# double-glide.net
KiCad netlist of a schematic drawn in EAGLE
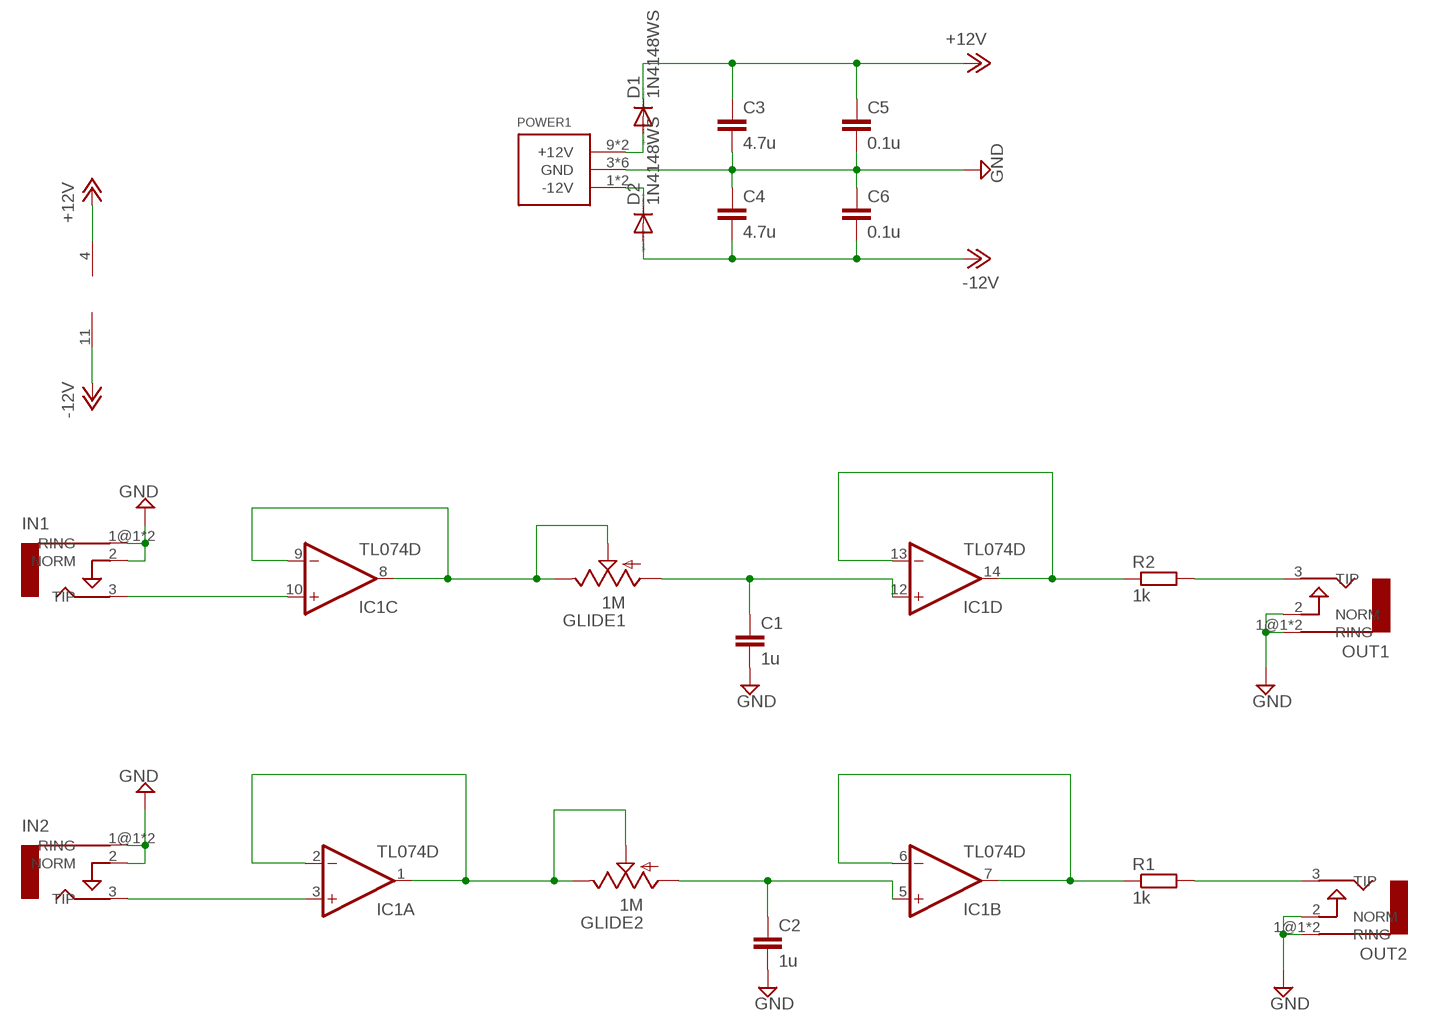
[diagram p0: schematic, sheet 1]

(export (version "E")
  (design (tool "Eeschema 10.0.6"))
  (components
    (comp (ref "C1")
      (value "1u")
      (footprint "eagle-import:C0805")
      (libsource (lib "eagle-import") (part "C-EUC0805"))
    )
    (comp (ref "C2")
      (value "1u")
      (footprint "eagle-import:C0805")
      (libsource (lib "eagle-import") (part "C-EUC0805"))
    )
    (comp (ref "C3")
      (value "4.7u")
      (footprint "eagle-import:C0805")
      (libsource (lib "eagle-import") (part "C-EUC0805"))
    )
    (comp (ref "C4")
      (value "4.7u")
      (footprint "eagle-import:C0805")
      (libsource (lib "eagle-import") (part "C-EUC0805"))
    )
    (comp (ref "C5")
      (value "0.1u")
      (footprint "eagle-import:C0805")
      (libsource (lib "eagle-import") (part "C-EUC0805"))
    )
    (comp (ref "C6")
      (value "0.1u")
      (footprint "eagle-import:C0805")
      (libsource (lib "eagle-import") (part "C-EUC0805"))
    )
    (comp (ref "D1")
      (value "1N4148WS")
      (footprint "eagle-import:SOD323-W")
      (libsource (lib "eagle-import") (part "DIODE-SOD323-W"))
    )
    (comp (ref "D2")
      (value "1N4148WS")
      (footprint "eagle-import:SOD323-W")
      (libsource (lib "eagle-import") (part "DIODE-SOD323-W"))
    )
    (comp (ref "GLIDE1")
      (value "1M")
      (footprint "eagle-import:9MM_SNAP-IN_POT")
      (libsource (lib "eagle-import") (part "9MM_SNAP-IN_POT_"))
    )
    (comp (ref "GLIDE2")
      (value "1M")
      (footprint "eagle-import:9MM_SNAP-IN_POT")
      (libsource (lib "eagle-import") (part "9MM_SNAP-IN_POT_"))
    )
    (comp (ref "IC1")
      (value "TL074D")
      (footprint "eagle-import:SO14")
      (libsource (lib "eagle-import") (part "TL074D"))
    )
    (comp (ref "IN1")
      (value "AUDIO-JACKERTHENVAR")
      (footprint "eagle-import:ERTHENVAR-JACK")
      (libsource (lib "eagle-import") (part "AUDIO-JACKERTHENVAR"))
    )
    (comp (ref "IN2")
      (value "AUDIO-JACKERTHENVAR")
      (footprint "eagle-import:ERTHENVAR-JACK")
      (libsource (lib "eagle-import") (part "AUDIO-JACKERTHENVAR"))
    )
    (comp (ref "OUT1")
      (value "AUDIO-JACKERTHENVAR")
      (footprint "eagle-import:ERTHENVAR-JACK")
      (libsource (lib "eagle-import") (part "AUDIO-JACKERTHENVAR"))
    )
    (comp (ref "OUT2")
      (value "AUDIO-JACKERTHENVAR")
      (footprint "eagle-import:ERTHENVAR-JACK")
      (libsource (lib "eagle-import") (part "AUDIO-JACKERTHENVAR"))
    )
    (comp (ref "POWER1")
      (value "POWER_SIMPLE10")
      (footprint "eagle-import:POWER_10")
      (libsource (lib "eagle-import") (part "POWER_SIMPLE10"))
    )
    (comp (ref "R1")
      (value "1k")
      (footprint "eagle-import:R0805")
      (libsource (lib "eagle-import") (part "R-EU_R0805"))
    )
    (comp (ref "R2")
      (value "1k")
      (footprint "eagle-import:R0805")
      (libsource (lib "eagle-import") (part "R-EU_R0805"))
    )
  )
  (nets
    (net (code "1") (name "+12V") (class "Default")
      (node (ref "C3") (pin "1") (pinfunction "1_1") (pintype "passive"))
      (node (ref "C5") (pin "1") (pinfunction "1_1") (pintype "passive"))
      (node (ref "D1") (pin "C") (pinfunction "C_C") (pintype "passive"))
      (node (ref "IC1") (pin "4") (pinfunction "V+_4") (pintype "power_in"))
    )
    (net (code "2") (name "-12V") (class "Default")
      (node (ref "C4") (pin "2") (pinfunction "2_2") (pintype "passive"))
      (node (ref "C6") (pin "2") (pinfunction "2_2") (pintype "passive"))
      (node (ref "D2") (pin "A") (pinfunction "A_A") (pintype "passive"))
      (node (ref "IC1") (pin "11") (pinfunction "V-_11") (pintype "power_in"))
    )
    (net (code "3") (name "GND") (class "Default")
      (node (ref "C1") (pin "2") (pinfunction "2_2") (pintype "passive"))
      (node (ref "C2") (pin "2") (pinfunction "2_2") (pintype "passive"))
      (node (ref "C3") (pin "2") (pinfunction "2_2") (pintype "passive"))
      (node (ref "C4") (pin "1") (pinfunction "1_1") (pintype "passive"))
      (node (ref "C5") (pin "2") (pinfunction "2_2") (pintype "passive"))
      (node (ref "C6") (pin "1") (pinfunction "1_1") (pintype "passive"))
      (node (ref "IN1") (pin "1@1") (pinfunction "RING_1@1") (pintype "bidirectional"))
      (node (ref "IN1") (pin "1@2") (pinfunction "RING_1@2") (pintype "bidirectional"))
      (node (ref "IN1") (pin "2") (pinfunction "NORM_2") (pintype "bidirectional"))
      (node (ref "IN2") (pin "1@1") (pinfunction "RING_1@1") (pintype "bidirectional"))
      (node (ref "IN2") (pin "1@2") (pinfunction "RING_1@2") (pintype "bidirectional"))
      (node (ref "IN2") (pin "2") (pinfunction "NORM_2") (pintype "bidirectional"))
      (node (ref "OUT1") (pin "1@1") (pinfunction "RING_1@1") (pintype "bidirectional"))
      (node (ref "OUT1") (pin "1@2") (pinfunction "RING_1@2") (pintype "bidirectional"))
      (node (ref "OUT1") (pin "2") (pinfunction "NORM_2") (pintype "bidirectional"))
      (node (ref "OUT2") (pin "1@1") (pinfunction "RING_1@1") (pintype "bidirectional"))
      (node (ref "OUT2") (pin "1@2") (pinfunction "RING_1@2") (pintype "bidirectional"))
      (node (ref "OUT2") (pin "2") (pinfunction "NORM_2") (pintype "bidirectional"))
      (node (ref "POWER1") (pin "3") (pinfunction "GND_3") (pintype "bidirectional"))
      (node (ref "POWER1") (pin "4") (pinfunction "GND_4") (pintype "bidirectional"))
      (node (ref "POWER1") (pin "5") (pinfunction "GND_5") (pintype "bidirectional"))
      (node (ref "POWER1") (pin "6") (pinfunction "GND_6") (pintype "bidirectional"))
      (node (ref "POWER1") (pin "7") (pinfunction "GND_7") (pintype "bidirectional"))
      (node (ref "POWER1") (pin "8") (pinfunction "GND_8") (pintype "bidirectional"))
    )
    (net (code "4") (name "Net-(D1-PadA)") (class "Default")
      (node (ref "D1") (pin "A") (pinfunction "A_A") (pintype "passive"))
      (node (ref "POWER1") (pin "10") (pinfunction "+12V_10") (pintype "bidirectional"))
      (node (ref "POWER1") (pin "9") (pinfunction "+12V_9") (pintype "bidirectional"))
    )
    (net (code "5") (name "Net-(D2-PadC)") (class "Default")
      (node (ref "D2") (pin "C") (pinfunction "C_C") (pintype "passive"))
      (node (ref "POWER1") (pin "1") (pinfunction "-12V_1") (pintype "bidirectional"))
      (node (ref "POWER1") (pin "2") (pinfunction "-12V_2") (pintype "bidirectional"))
    )
    (net (code "6") (name "Net-(GLIDE1-A)") (class "Default")
      (node (ref "C1") (pin "1") (pinfunction "1_1") (pintype "passive"))
      (node (ref "GLIDE1") (pin "1") (pinfunction "A_1") (pintype "passive"))
      (node (ref "IC1") (pin "12") (pinfunction "+IN_12") (pintype "input"))
    )
    (net (code "7") (name "Net-(GLIDE1-E)") (class "Default")
      (node (ref "GLIDE1") (pin "2") (pinfunction "S_2") (pintype "passive"))
      (node (ref "GLIDE1") (pin "3") (pinfunction "E_3") (pintype "passive"))
      (node (ref "IC1") (pin "8") (pinfunction "OUT_8") (pintype "output"))
      (node (ref "IC1") (pin "9") (pinfunction "-IN_9") (pintype "input"))
    )
    (net (code "8") (name "Net-(GLIDE2-A)") (class "Default")
      (node (ref "C2") (pin "1") (pinfunction "1_1") (pintype "passive"))
      (node (ref "GLIDE2") (pin "1") (pinfunction "A_1") (pintype "passive"))
      (node (ref "IC1") (pin "5") (pinfunction "+IN_5") (pintype "input"))
    )
    (net (code "9") (name "Net-(GLIDE2-E)") (class "Default")
      (node (ref "GLIDE2") (pin "2") (pinfunction "S_2") (pintype "passive"))
      (node (ref "GLIDE2") (pin "3") (pinfunction "E_3") (pintype "passive"))
      (node (ref "IC1") (pin "1") (pinfunction "OUT_1") (pintype "output"))
      (node (ref "IC1") (pin "2") (pinfunction "-IN_2") (pintype "input"))
    )
    (net (code "10") (name "Net-(IC1A-+IN)") (class "Default")
      (node (ref "IC1") (pin "3") (pinfunction "+IN_3") (pintype "input"))
      (node (ref "IN2") (pin "3") (pinfunction "TIP_3") (pintype "bidirectional"))
    )
    (net (code "11") (name "Net-(IC1B--IN)") (class "Default")
      (node (ref "IC1") (pin "6") (pinfunction "-IN_6") (pintype "input"))
      (node (ref "IC1") (pin "7") (pinfunction "OUT_7") (pintype "output"))
      (node (ref "R1") (pin "1") (pinfunction "1_1") (pintype "passive"))
    )
    (net (code "12") (name "Net-(IC1C-+IN)") (class "Default")
      (node (ref "IC1") (pin "10") (pinfunction "+IN_10") (pintype "input"))
      (node (ref "IN1") (pin "3") (pinfunction "TIP_3") (pintype "bidirectional"))
    )
    (net (code "13") (name "Net-(IC1D--IN)") (class "Default")
      (node (ref "IC1") (pin "13") (pinfunction "-IN_13") (pintype "input"))
      (node (ref "IC1") (pin "14") (pinfunction "OUT_14") (pintype "output"))
      (node (ref "R2") (pin "1") (pinfunction "1_1") (pintype "passive"))
    )
    (net (code "14") (name "Net-(OUT1-TIP)") (class "Default")
      (node (ref "OUT1") (pin "3") (pinfunction "TIP_3") (pintype "bidirectional"))
      (node (ref "R2") (pin "2") (pinfunction "2_2") (pintype "passive"))
    )
    (net (code "15") (name "Net-(OUT2-TIP)") (class "Default")
      (node (ref "OUT2") (pin "3") (pinfunction "TIP_3") (pintype "bidirectional"))
      (node (ref "R1") (pin "2") (pinfunction "2_2") (pintype "passive"))
    )
  )
)
